# ddr3_if.net
KiCad netlist of a schematic drawn in Altium Designer
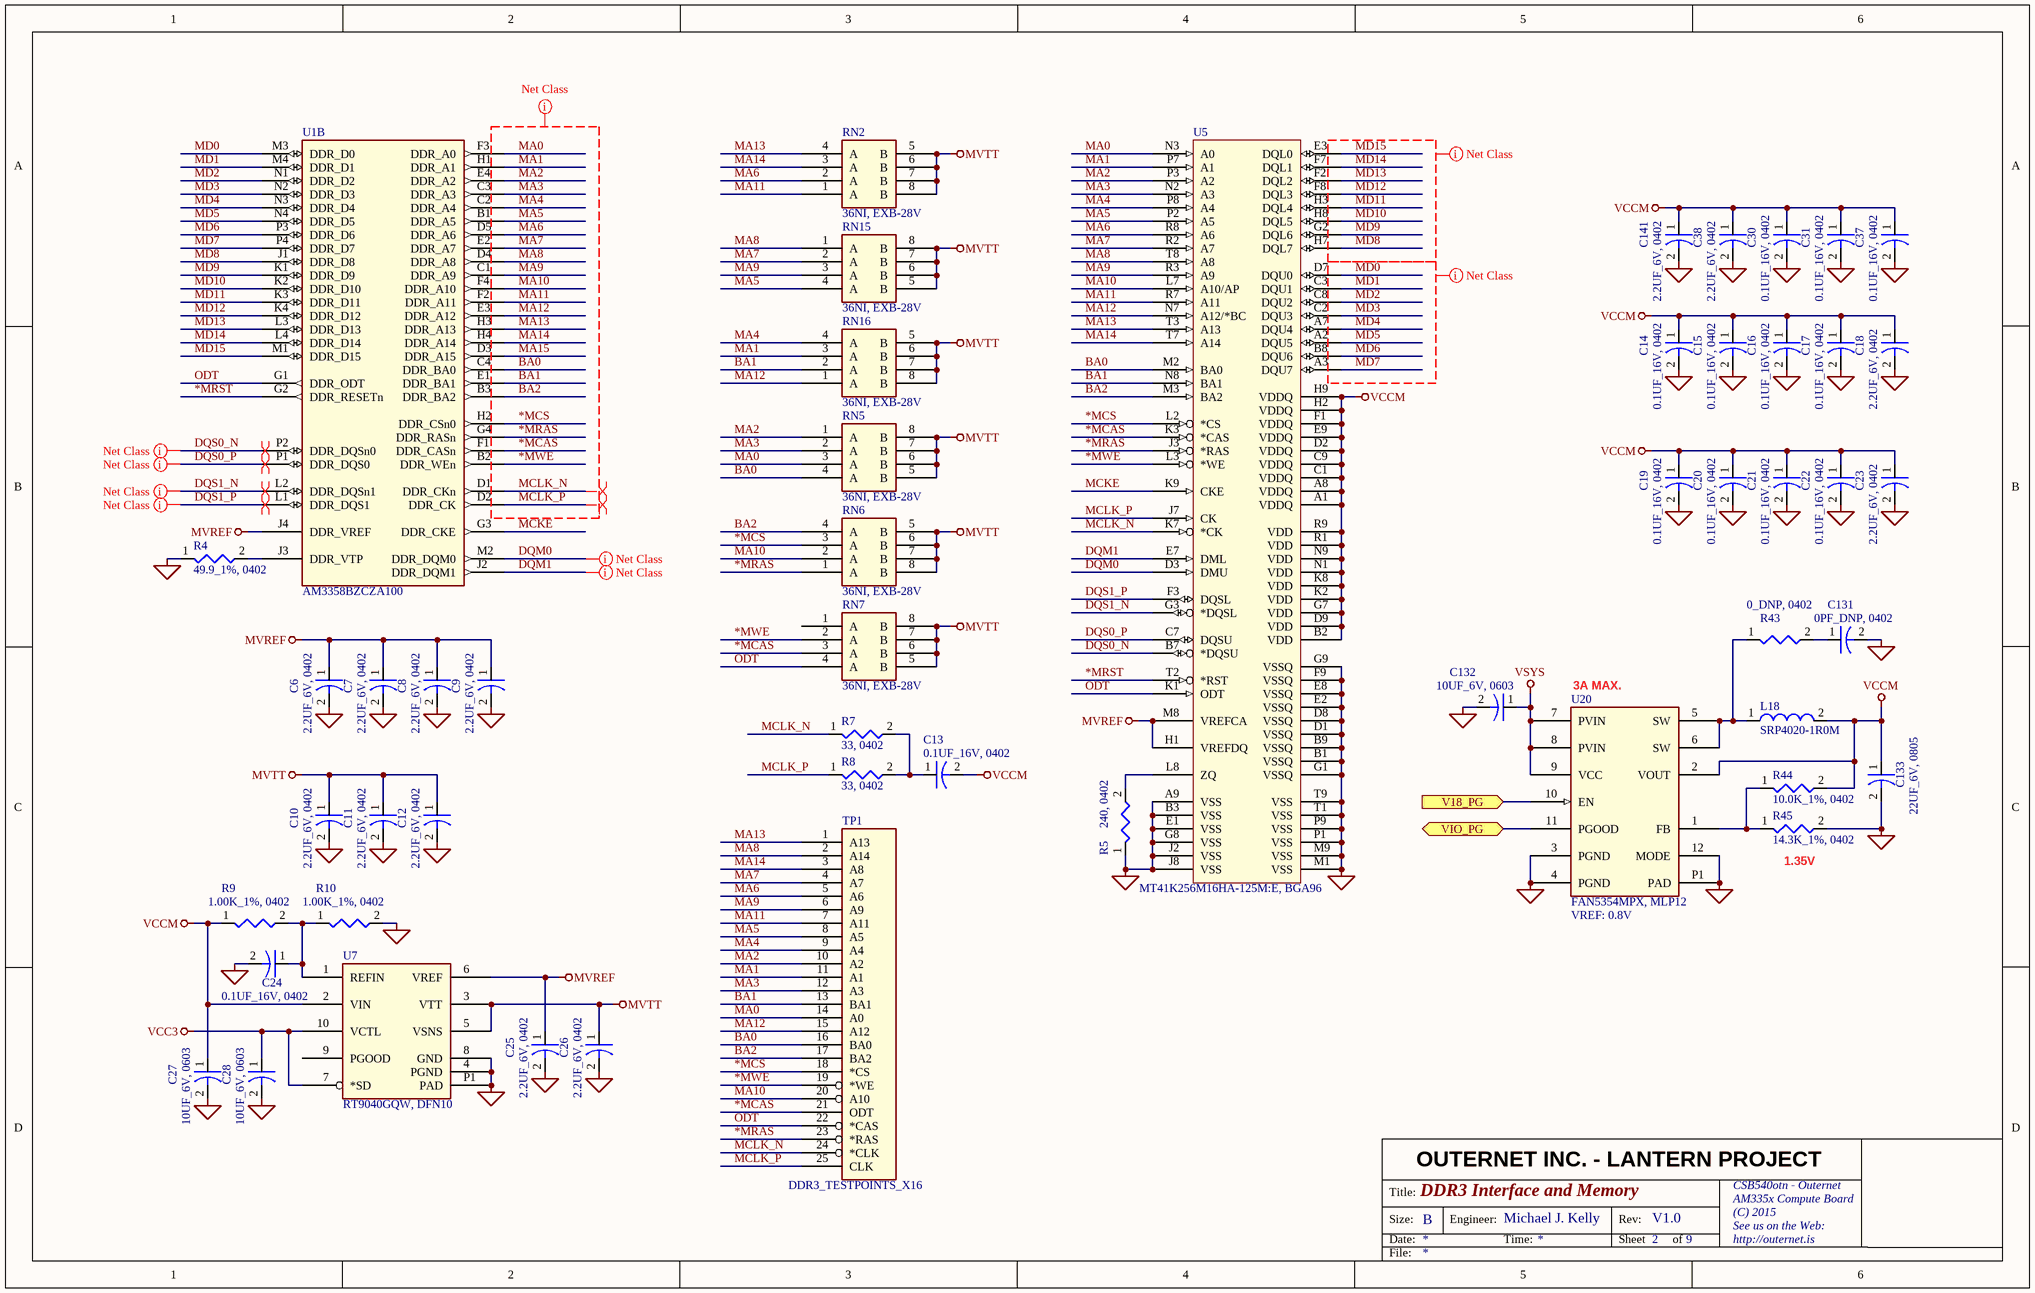
[diagram p0: ddr3_if.SchDoc]

(export (version "E")
  (design (tool "Eeschema 10.0.6"))
  (components
    (comp (ref "C6")
      (value "2.2UF_6V, 0402")
      (footprint "0402C")
      (description "CAP - 0402 PKG")
      (libsource (lib "COGENT_Library") (part "2.2UF_6V, 0402"))
    )
    (comp (ref "C7")
      (value "2.2UF_6V, 0402")
      (footprint "0402C")
      (description "CAP - 0402 PKG")
      (libsource (lib "COGENT_Library") (part "2.2UF_6V, 0402"))
    )
    (comp (ref "C8")
      (value "2.2UF_6V, 0402")
      (footprint "0402C")
      (description "CAP - 0402 PKG")
      (libsource (lib "COGENT_Library") (part "2.2UF_6V, 0402"))
    )
    (comp (ref "C9")
      (value "2.2UF_6V, 0402")
      (footprint "0402C")
      (description "CAP - 0402 PKG")
      (libsource (lib "COGENT_Library") (part "2.2UF_6V, 0402"))
    )
    (comp (ref "C10")
      (value "2.2UF_6V, 0402")
      (footprint "0402C")
      (description "CAP - 0402 PKG")
      (libsource (lib "COGENT_Library") (part "2.2UF_6V, 0402"))
    )
    (comp (ref "C11")
      (value "2.2UF_6V, 0402")
      (footprint "0402C")
      (description "CAP - 0402 PKG")
      (libsource (lib "COGENT_Library") (part "2.2UF_6V, 0402"))
    )
    (comp (ref "C12")
      (value "2.2UF_6V, 0402")
      (footprint "0402C")
      (description "CAP - 0402 PKG")
      (libsource (lib "COGENT_Library") (part "2.2UF_6V, 0402"))
    )
    (comp (ref "C13")
      (value "0.1UF_16V, 0402")
      (footprint "0402C")
      (description "CAP - 0402 PKG")
      (libsource (lib "COGENT_Library") (part "0.1UF_16V, 0402"))
    )
    (comp (ref "C14")
      (value "0.1UF_16V, 0402")
      (footprint "0402C")
      (description "CAP - 0402 PKG")
      (libsource (lib "COGENT_Library") (part "0.1UF_16V, 0402"))
    )
    (comp (ref "C15")
      (value "0.1UF_16V, 0402")
      (footprint "0402C")
      (description "CAP - 0402 PKG")
      (libsource (lib "COGENT_Library") (part "0.1UF_16V, 0402"))
    )
    (comp (ref "C16")
      (value "0.1UF_16V, 0402")
      (footprint "0402C")
      (description "CAP - 0402 PKG")
      (libsource (lib "COGENT_Library") (part "0.1UF_16V, 0402"))
    )
    (comp (ref "C17")
      (value "0.1UF_16V, 0402")
      (footprint "0402C")
      (description "CAP - 0402 PKG")
      (libsource (lib "COGENT_Library") (part "0.1UF_16V, 0402"))
    )
    (comp (ref "C18")
      (value "2.2UF_6V, 0402")
      (footprint "0402C")
      (description "CAP - 0402 PKG")
      (libsource (lib "COGENT_Library") (part "2.2UF_6V, 0402"))
    )
    (comp (ref "C19")
      (value "0.1UF_16V, 0402")
      (footprint "0402C")
      (description "CAP - 0402 PKG")
      (libsource (lib "COGENT_Library") (part "0.1UF_16V, 0402"))
    )
    (comp (ref "C20")
      (value "0.1UF_16V, 0402")
      (footprint "0402C")
      (description "CAP - 0402 PKG")
      (libsource (lib "COGENT_Library") (part "0.1UF_16V, 0402"))
    )
    (comp (ref "C21")
      (value "0.1UF_16V, 0402")
      (footprint "0402C")
      (description "CAP - 0402 PKG")
      (libsource (lib "COGENT_Library") (part "0.1UF_16V, 0402"))
    )
    (comp (ref "C22")
      (value "0.1UF_16V, 0402")
      (footprint "0402C")
      (description "CAP - 0402 PKG")
      (libsource (lib "COGENT_Library") (part "0.1UF_16V, 0402"))
    )
    (comp (ref "C23")
      (value "2.2UF_6V, 0402")
      (footprint "0402C")
      (description "CAP - 0402 PKG")
      (libsource (lib "COGENT_Library") (part "2.2UF_6V, 0402"))
    )
    (comp (ref "C24")
      (value "0.1UF_16V, 0402")
      (footprint "0402C")
      (description "CAP - 0402 PKG")
      (libsource (lib "COGENT_Library") (part "0.1UF_16V, 0402"))
    )
    (comp (ref "C25")
      (value "2.2UF_6V, 0402")
      (footprint "0402C")
      (description "CAP - 0402 PKG")
      (libsource (lib "COGENT_Library") (part "2.2UF_6V, 0402"))
    )
    (comp (ref "C26")
      (value "2.2UF_6V, 0402")
      (footprint "0402C")
      (description "CAP - 0402 PKG")
      (libsource (lib "COGENT_Library") (part "2.2UF_6V, 0402"))
    )
    (comp (ref "C27")
      (value "10UF_6V, 0603")
      (footprint "0603C")
      (description "CAP - 0603 PKG")
      (libsource (lib "COGENT_Library") (part "10UF_6V, 0603"))
    )
    (comp (ref "C28")
      (value "10UF_6V, 0603")
      (footprint "0603C")
      (description "CAP - 0603 PKG")
      (libsource (lib "COGENT_Library") (part "10UF_6V, 0603"))
    )
    (comp (ref "C30")
      (value "0.1UF_16V, 0402")
      (footprint "0402C")
      (description "CAP - 0402 PKG")
      (libsource (lib "COGENT_Library") (part "0.1UF_16V, 0402"))
    )
    (comp (ref "C31")
      (value "0.1UF_16V, 0402")
      (footprint "0402C")
      (description "CAP - 0402 PKG")
      (libsource (lib "COGENT_Library") (part "0.1UF_16V, 0402"))
    )
    (comp (ref "C37")
      (value "0.1UF_16V, 0402")
      (footprint "0402C")
      (description "CAP - 0402 PKG")
      (libsource (lib "COGENT_Library") (part "0.1UF_16V, 0402"))
    )
    (comp (ref "C38")
      (value "2.2UF_6V, 0402")
      (footprint "0402C")
      (description "CAP - 0402 PKG")
      (libsource (lib "COGENT_Library") (part "2.2UF_6V, 0402"))
    )
    (comp (ref "C131")
      (value "0PF_DNP, 0402")
      (footprint "0402C")
      (description "CAP - 0402 PKG")
      (libsource (lib "COGENT_Library") (part "0PF_DNP, 0402"))
    )
    (comp (ref "C132")
      (value "10UF_6V, 0603")
      (footprint "0603C")
      (description "CAP - 0603 PKG")
      (libsource (lib "COGENT_Library") (part "10UF_6V, 0603"))
    )
    (comp (ref "C133")
      (value "22UF_6V, 0805")
      (footprint "0805C")
      (description "CAP - 0805 PKG")
      (libsource (lib "COGENT_Library") (part "22UF_6V, 0805"))
    )
    (comp (ref "C141")
      (value "2.2UF_6V, 0402")
      (footprint "0402C")
      (description "CAP - 0402 PKG")
      (libsource (lib "COGENT_Library") (part "2.2UF_6V, 0402"))
    )
    (comp (ref "L18")
      (value "SRP4020-1R0M")
      (footprint "SRP4020")
      (description "INDUCTOR - 1.0UH, 5/6A, 4MM x 4MM x 2MM, 22mohm")
      (libsource (lib "COGENT_Library") (part "SRP4020-1R0M"))
    )
    (comp (ref "R4")
      (value "49.9_1%, 0402")
      (footprint "0402R")
      (description "RES - 0402 PKG")
      (libsource (lib "COGENT_Library") (part "49.9_1%, 0402"))
    )
    (comp (ref "R5")
      (value "240, 0402")
      (footprint "0402R")
      (description "RES - 0402 PKG")
      (libsource (lib "COGENT_Library") (part "240, 0402"))
    )
    (comp (ref "R7")
      (value "33, 0402")
      (footprint "0402R")
      (description "RES - 0402 PKG")
      (libsource (lib "COGENT_Library") (part "33, 0402"))
    )
    (comp (ref "R8")
      (value "33, 0402")
      (footprint "0402R")
      (description "RES - 0402 PKG")
      (libsource (lib "COGENT_Library") (part "33, 0402"))
    )
    (comp (ref "R9")
      (value "1.00K_1%, 0402")
      (footprint "0402R")
      (description "RES - 0402 PKG")
      (libsource (lib "COGENT_Library") (part "1.00K_1%, 0402"))
    )
    (comp (ref "R10")
      (value "1.00K_1%, 0402")
      (footprint "0402R")
      (description "RES - 0402 PKG")
      (libsource (lib "COGENT_Library") (part "1.00K_1%, 0402"))
    )
    (comp (ref "R43")
      (value "0_DNP, 0402")
      (footprint "0402R")
      (description "RES - 0402 PKG, DO NOT POPULATE BY DEFAULT")
      (libsource (lib "COGENT_Library") (part "0_DNP, 0402"))
    )
    (comp (ref "R44")
      (value "10.0K_1%, 0402")
      (footprint "0402R")
      (description "RES - 0402 PKG")
      (libsource (lib "COGENT_Library") (part "10.0K_1%, 0402"))
    )
    (comp (ref "R45")
      (value "14.3K_1%, 0402")
      (footprint "0402R")
      (description "RES - 0402 PKG")
      (libsource (lib "COGENT_Library") (part "14.3K_1%, 0402"))
    )
    (comp (ref "RN2")
      (value "36NI, EXB-28V")
      (footprint "EXB-28V")
      (description "RES NET, 4 INDIVIDUAL, EXB-28V")
      (libsource (lib "COGENT_Library") (part "36NI, EXB-28V"))
    )
    (comp (ref "RN5")
      (value "36NI, EXB-28V")
      (footprint "EXB-28V")
      (description "RES NET, 4 INDIVIDUAL, EXB-28V")
      (libsource (lib "") (part "36NI, EXB-28V_1"))
    )
    (comp (ref "RN6")
      (value "36NI, EXB-28V")
      (footprint "EXB-28V")
      (description "RES NET, 4 INDIVIDUAL, EXB-28V")
      (libsource (lib "COGENT_Library") (part "36NI, EXB-28V"))
    )
    (comp (ref "RN7")
      (value "36NI, EXB-28V")
      (footprint "EXB-28V")
      (description "RES NET, 4 INDIVIDUAL, EXB-28V")
      (libsource (lib "") (part "36NI, EXB-28V_1"))
    )
    (comp (ref "RN15")
      (value "36NI, EXB-28V")
      (footprint "EXB-28V")
      (description "RES NET, 4 INDIVIDUAL, EXB-28V")
      (libsource (lib "") (part "36NI, EXB-28V_1"))
    )
    (comp (ref "RN16")
      (value "36NI, EXB-28V")
      (footprint "EXB-28V")
      (description "RES NET, 4 INDIVIDUAL, EXB-28V")
      (libsource (lib "COGENT_Library") (part "36NI, EXB-28V"))
    )
    (comp (ref "TP1")
      (value "DDR3_TESTPOINTS_X16")
      (footprint "DDR2-TP")
      (description "MISC - DDR3 ROUTING PATTERN, 16-BIT")
      (libsource (lib "COGENT_Library") (part "DDR3_TESTPOINTS_X16"))
    )
    (comp (ref "U1")
      (value "AM3358BZCZA100")
      (footprint "BGA324x18")
      (description "MPU - CORTEX-A8 CORE, SDIO, GIGe, USB x2, UART x3, CAN, 2D/3D")
      (libsource (lib "COGENT_Library") (part "AM3358BZCZA100"))
    )
    (comp (ref "U5")
      (value "MT41K256M16HA-125M:E, BGA96")
      (footprint "BGA96_DDR3_X16")
      (description "SDRAM - 4GBIT, DDR3/L-1600, x16")
      (libsource (lib "COGENT_Library") (part "MT41K256M16HA-125M{colon}E, BGA96"))
    )
    (comp (ref "U7")
      (value "RT9040GQW, DFN10")
      (footprint "DFN10")
      (description "LDO - DDR2/3 VREF AND VTT, 3A")
      (libsource (lib "COGENT_Library") (part "RT9040GQW, DFN10"))
    )
    (comp (ref "U20")
      (value "FAN5354MPX, MLP12")
      (footprint "mlp12")
      (description "SWITCHER - 270ua Iq, 3A, 2.7V TO 5.5V IN, 0.8V TO VIN OUT")
      (fields (field (name "VREF") "0.8V"))
      (libsource (lib "COGENT_Library") (part "FAN5354MPX, MLP12"))
    )
  )
  (nets
    (net (code "1") (name "/*MCAS") (class "Default")
      (node (ref "RN7") (pin "3") (pinfunction "A_3") (pintype "passive"))
      (node (ref "TP1") (pin "21") (pinfunction "ODT_21") (pintype "passive"))
      (node (ref "U1") (pin "F1") (pinfunction "DDR_CASn_F1") (pintype "output"))
      (node (ref "U5") (pin "K3") (pinfunction "*CAS_K3") (pintype "input"))
    )
    (net (code "2") (name "/*MCS") (class "Default")
      (node (ref "RN6") (pin "3") (pinfunction "A_3") (pintype "passive"))
      (node (ref "TP1") (pin "18") (pinfunction "*CS_18") (pintype "passive"))
      (node (ref "U1") (pin "H2") (pinfunction "DDR_CSn0_H2") (pintype "output"))
      (node (ref "U5") (pin "L2") (pinfunction "*CS_L2") (pintype "input"))
    )
    (net (code "3") (name "/*MRAS") (class "Default")
      (node (ref "RN6") (pin "1") (pinfunction "A_1") (pintype "passive"))
      (node (ref "TP1") (pin "23") (pinfunction "*RAS_23") (pintype "passive"))
      (node (ref "U1") (pin "G4") (pinfunction "DDR_RASn_G4") (pintype "output"))
      (node (ref "U5") (pin "J3") (pinfunction "*RAS_J3") (pintype "input"))
    )
    (net (code "4") (name "/*MRST") (class "Default")
      (node (ref "U1") (pin "G2") (pinfunction "DDR_RESETn_G2") (pintype "output"))
      (node (ref "U5") (pin "T2") (pinfunction "*RST_T2") (pintype "input"))
    )
    (net (code "5") (name "/*MWE") (class "Default")
      (node (ref "RN7") (pin "2") (pinfunction "A_2") (pintype "passive"))
      (node (ref "TP1") (pin "19") (pinfunction "*WE_19") (pintype "passive"))
      (node (ref "U1") (pin "B2") (pinfunction "DDR_WEn_B2") (pintype "output"))
      (node (ref "U5") (pin "L3") (pinfunction "*WE_L3") (pintype "input"))
    )
    (net (code "6") (name "/BA0") (class "Default")
      (node (ref "RN5") (pin "4") (pinfunction "A_4") (pintype "passive"))
      (node (ref "TP1") (pin "16") (pinfunction "BA0_16") (pintype "passive"))
      (node (ref "U1") (pin "C4") (pinfunction "DDR_BA0_C4") (pintype "output"))
      (node (ref "U5") (pin "M2") (pinfunction "BA0_M2") (pintype "input"))
    )
    (net (code "7") (name "/BA1") (class "Default")
      (node (ref "RN16") (pin "2") (pinfunction "A_2") (pintype "passive"))
      (node (ref "TP1") (pin "13") (pinfunction "BA1_13") (pintype "passive"))
      (node (ref "U1") (pin "E1") (pinfunction "DDR_BA1_E1") (pintype "output"))
      (node (ref "U5") (pin "N8") (pinfunction "BA1_N8") (pintype "input"))
    )
    (net (code "8") (name "/BA2") (class "Default")
      (node (ref "RN6") (pin "4") (pinfunction "A_4") (pintype "passive"))
      (node (ref "TP1") (pin "17") (pinfunction "BA2_17") (pintype "passive"))
      (node (ref "U1") (pin "B3") (pinfunction "DDR_BA2_B3") (pintype "output"))
      (node (ref "U5") (pin "M3") (pinfunction "BA2_M3") (pintype "input"))
    )
    (net (code "9") (name "/DQM0") (class "Default")
      (node (ref "U1") (pin "M2") (pinfunction "DDR_DQM0_M2") (pintype "output"))
      (node (ref "U5") (pin "D3") (pinfunction "DMU_D3") (pintype "input"))
    )
    (net (code "10") (name "/DQM1") (class "Default")
      (node (ref "U1") (pin "J2") (pinfunction "DDR_DQM1_J2") (pintype "output"))
      (node (ref "U5") (pin "E7") (pinfunction "DML_E7") (pintype "input"))
    )
    (net (code "11") (name "/DQS0_N") (class "Default")
      (node (ref "U1") (pin "P2") (pinfunction "DDR_DQSn0_P2") (pintype "bidirectional"))
      (node (ref "U5") (pin "B7") (pinfunction "*DQSU_B7") (pintype "bidirectional"))
    )
    (net (code "12") (name "/DQS0_P") (class "Default")
      (node (ref "U1") (pin "P1") (pinfunction "DDR_DQS0_P1") (pintype "bidirectional"))
      (node (ref "U5") (pin "C7") (pinfunction "DQSU_C7") (pintype "bidirectional"))
    )
    (net (code "13") (name "/DQS1_N") (class "Default")
      (node (ref "U1") (pin "L2") (pinfunction "DDR_DQSn1_L2") (pintype "bidirectional"))
      (node (ref "U5") (pin "G3") (pinfunction "*DQSL_G3") (pintype "bidirectional"))
    )
    (net (code "14") (name "/DQS1_P") (class "Default")
      (node (ref "U1") (pin "L1") (pinfunction "DDR_DQS1_L1") (pintype "bidirectional"))
      (node (ref "U5") (pin "F3") (pinfunction "DQSL_F3") (pintype "bidirectional"))
    )
    (net (code "15") (name "/MA0") (class "Default")
      (node (ref "RN5") (pin "3") (pinfunction "A_3") (pintype "passive"))
      (node (ref "TP1") (pin "14") (pinfunction "A0_14") (pintype "passive"))
      (node (ref "U1") (pin "F3") (pinfunction "DDR_A0_F3") (pintype "output"))
      (node (ref "U5") (pin "N3") (pinfunction "A0_N3") (pintype "input"))
    )
    (net (code "16") (name "/MA1") (class "Default")
      (node (ref "RN16") (pin "3") (pinfunction "A_3") (pintype "passive"))
      (node (ref "TP1") (pin "11") (pinfunction "A1_11") (pintype "passive"))
      (node (ref "U1") (pin "H1") (pinfunction "DDR_A1_H1") (pintype "output"))
      (node (ref "U5") (pin "P7") (pinfunction "A1_P7") (pintype "input"))
    )
    (net (code "17") (name "/MA2") (class "Default")
      (node (ref "RN5") (pin "1") (pinfunction "A_1") (pintype "passive"))
      (node (ref "TP1") (pin "10") (pinfunction "A2_10") (pintype "passive"))
      (node (ref "U1") (pin "E4") (pinfunction "DDR_A2_E4") (pintype "output"))
      (node (ref "U5") (pin "P3") (pinfunction "A2_P3") (pintype "input"))
    )
    (net (code "18") (name "/MA3") (class "Default")
      (node (ref "RN5") (pin "2") (pinfunction "A_2") (pintype "passive"))
      (node (ref "TP1") (pin "12") (pinfunction "A3_12") (pintype "passive"))
      (node (ref "U1") (pin "C3") (pinfunction "DDR_A3_C3") (pintype "output"))
      (node (ref "U5") (pin "N2") (pinfunction "A3_N2") (pintype "input"))
    )
    (net (code "19") (name "/MA4") (class "Default")
      (node (ref "RN16") (pin "4") (pinfunction "A_4") (pintype "passive"))
      (node (ref "TP1") (pin "9") (pinfunction "A4_9") (pintype "passive"))
      (node (ref "U1") (pin "C2") (pinfunction "DDR_A4_C2") (pintype "output"))
      (node (ref "U5") (pin "P8") (pinfunction "A4_P8") (pintype "input"))
    )
    (net (code "20") (name "/MA5") (class "Default")
      (node (ref "RN15") (pin "4") (pinfunction "A_4") (pintype "passive"))
      (node (ref "TP1") (pin "8") (pinfunction "A5_8") (pintype "passive"))
      (node (ref "U1") (pin "B1") (pinfunction "DDR_A5_B1") (pintype "output"))
      (node (ref "U5") (pin "P2") (pinfunction "A5_P2") (pintype "input"))
    )
    (net (code "21") (name "/MA6") (class "Default")
      (node (ref "RN2") (pin "2") (pinfunction "A_2") (pintype "passive"))
      (node (ref "TP1") (pin "5") (pinfunction "A6_5") (pintype "passive"))
      (node (ref "U1") (pin "D5") (pinfunction "DDR_A6_D5") (pintype "output"))
      (node (ref "U5") (pin "R8") (pinfunction "A6_R8") (pintype "input"))
    )
    (net (code "22") (name "/MA7") (class "Default")
      (node (ref "RN15") (pin "2") (pinfunction "A_2") (pintype "passive"))
      (node (ref "TP1") (pin "4") (pinfunction "A7_4") (pintype "passive"))
      (node (ref "U1") (pin "E2") (pinfunction "DDR_A7_E2") (pintype "output"))
      (node (ref "U5") (pin "R2") (pinfunction "A7_R2") (pintype "input"))
    )
    (net (code "23") (name "/MA8") (class "Default")
      (node (ref "RN15") (pin "1") (pinfunction "A_1") (pintype "passive"))
      (node (ref "TP1") (pin "2") (pinfunction "A14_2") (pintype "passive"))
      (node (ref "U1") (pin "D4") (pinfunction "DDR_A8_D4") (pintype "output"))
      (node (ref "U5") (pin "T8") (pinfunction "A8_T8") (pintype "input"))
    )
    (net (code "24") (name "/MA9") (class "Default")
      (node (ref "RN15") (pin "3") (pinfunction "A_3") (pintype "passive"))
      (node (ref "TP1") (pin "6") (pinfunction "A9_6") (pintype "passive"))
      (node (ref "U1") (pin "C1") (pinfunction "DDR_A9_C1") (pintype "output"))
      (node (ref "U5") (pin "R3") (pinfunction "A9_R3") (pintype "input"))
    )
    (net (code "25") (name "/MA10") (class "Default")
      (node (ref "RN6") (pin "2") (pinfunction "A_2") (pintype "passive"))
      (node (ref "TP1") (pin "20") (pinfunction "A10_20") (pintype "passive"))
      (node (ref "U1") (pin "F4") (pinfunction "DDR_A10_F4") (pintype "output"))
      (node (ref "U5") (pin "L7") (pinfunction "A10/AP_L7") (pintype "input"))
    )
    (net (code "26") (name "/MA11") (class "Default")
      (node (ref "RN2") (pin "1") (pinfunction "A_1") (pintype "passive"))
      (node (ref "TP1") (pin "7") (pinfunction "A11_7") (pintype "passive"))
      (node (ref "U1") (pin "F2") (pinfunction "DDR_A11_F2") (pintype "output"))
      (node (ref "U5") (pin "R7") (pinfunction "A11_R7") (pintype "input"))
    )
    (net (code "27") (name "/MA12") (class "Default")
      (node (ref "RN16") (pin "1") (pinfunction "A_1") (pintype "passive"))
      (node (ref "TP1") (pin "15") (pinfunction "A12_15") (pintype "passive"))
      (node (ref "U1") (pin "E3") (pinfunction "DDR_A12_E3") (pintype "output"))
      (node (ref "U5") (pin "N7") (pinfunction "A12/*BC_N7") (pintype "input"))
    )
    (net (code "28") (name "/MA13") (class "Default")
      (node (ref "RN2") (pin "4") (pinfunction "A_4") (pintype "passive"))
      (node (ref "TP1") (pin "1") (pinfunction "A13_1") (pintype "passive"))
      (node (ref "U1") (pin "H3") (pinfunction "DDR_A13_H3") (pintype "output"))
      (node (ref "U5") (pin "T3") (pinfunction "A13_T3") (pintype "input"))
    )
    (net (code "29") (name "/MA14") (class "Default")
      (node (ref "RN2") (pin "3") (pinfunction "A_3") (pintype "passive"))
      (node (ref "TP1") (pin "3") (pinfunction "A8_3") (pintype "passive"))
      (node (ref "U1") (pin "H4") (pinfunction "DDR_A14_H4") (pintype "output"))
      (node (ref "U5") (pin "T7") (pinfunction "A14_T7") (pintype "input"))
    )
    (net (code "30") (name "/MA15") (class "Default")
      (node (ref "U1") (pin "D3") (pinfunction "DDR_A15_D3") (pintype "output"))
    )
    (net (code "31") (name "/MCKE") (class "Default")
      (node (ref "U1") (pin "G3") (pinfunction "DDR_CKE_G3") (pintype "output"))
      (node (ref "U5") (pin "K9") (pinfunction "CKE_K9") (pintype "input"))
    )
    (net (code "32") (name "/MCLK_N") (class "Default")
      (node (ref "R7") (pin "1") (pinfunction "1_1") (pintype "passive"))
      (node (ref "TP1") (pin "24") (pinfunction "*CLK_24") (pintype "passive"))
      (node (ref "U1") (pin "D1") (pinfunction "DDR_CKn_D1") (pintype "output"))
      (node (ref "U5") (pin "K7") (pinfunction "*CK_K7") (pintype "input"))
    )
    (net (code "33") (name "/MCLK_P") (class "Default")
      (node (ref "R8") (pin "1") (pinfunction "1_1") (pintype "passive"))
      (node (ref "TP1") (pin "25") (pinfunction "CLK_25") (pintype "passive"))
      (node (ref "U1") (pin "D2") (pinfunction "DDR_CK_D2") (pintype "output"))
      (node (ref "U5") (pin "J7") (pinfunction "CK_J7") (pintype "input"))
    )
    (net (code "34") (name "/MD0") (class "Default")
      (node (ref "U1") (pin "M3") (pinfunction "DDR_D0_M3") (pintype "bidirectional"))
      (node (ref "U5") (pin "D7") (pinfunction "DQU0_D7") (pintype "bidirectional"))
    )
    (net (code "35") (name "/MD1") (class "Default")
      (node (ref "U1") (pin "M4") (pinfunction "DDR_D1_M4") (pintype "bidirectional"))
      (node (ref "U5") (pin "C3") (pinfunction "DQU1_C3") (pintype "bidirectional"))
    )
    (net (code "36") (name "/MD2") (class "Default")
      (node (ref "U1") (pin "N1") (pinfunction "DDR_D2_N1") (pintype "bidirectional"))
      (node (ref "U5") (pin "C8") (pinfunction "DQU2_C8") (pintype "bidirectional"))
    )
    (net (code "37") (name "/MD3") (class "Default")
      (node (ref "U1") (pin "N2") (pinfunction "DDR_D3_N2") (pintype "bidirectional"))
      (node (ref "U5") (pin "C2") (pinfunction "DQU3_C2") (pintype "bidirectional"))
    )
    (net (code "38") (name "/MD4") (class "Default")
      (node (ref "U1") (pin "N3") (pinfunction "DDR_D4_N3") (pintype "bidirectional"))
      (node (ref "U5") (pin "A7") (pinfunction "DQU4_A7") (pintype "bidirectional"))
    )
    (net (code "39") (name "/MD5") (class "Default")
      (node (ref "U1") (pin "N4") (pinfunction "DDR_D5_N4") (pintype "bidirectional"))
      (node (ref "U5") (pin "A2") (pinfunction "DQU5_A2") (pintype "bidirectional"))
    )
    (net (code "40") (name "/MD6") (class "Default")
      (node (ref "U1") (pin "P3") (pinfunction "DDR_D6_P3") (pintype "bidirectional"))
      (node (ref "U5") (pin "B8") (pinfunction "DQU6_B8") (pintype "bidirectional"))
    )
    (net (code "41") (name "/MD7") (class "Default")
      (node (ref "U1") (pin "P4") (pinfunction "DDR_D7_P4") (pintype "bidirectional"))
      (node (ref "U5") (pin "A3") (pinfunction "DQU7_A3") (pintype "bidirectional"))
    )
    (net (code "42") (name "/MD8") (class "Default")
      (node (ref "U1") (pin "J1") (pinfunction "DDR_D8_J1") (pintype "bidirectional"))
      (node (ref "U5") (pin "H7") (pinfunction "DQL7_H7") (pintype "bidirectional"))
    )
    (net (code "43") (name "/MD9") (class "Default")
      (node (ref "U1") (pin "K1") (pinfunction "DDR_D9_K1") (pintype "bidirectional"))
      (node (ref "U5") (pin "G2") (pinfunction "DQL6_G2") (pintype "bidirectional"))
    )
    (net (code "44") (name "/MD10") (class "Default")
      (node (ref "U1") (pin "K2") (pinfunction "DDR_D10_K2") (pintype "bidirectional"))
      (node (ref "U5") (pin "H8") (pinfunction "DQL5_H8") (pintype "bidirectional"))
    )
    (net (code "45") (name "/MD11") (class "Default")
      (node (ref "U1") (pin "K3") (pinfunction "DDR_D11_K3") (pintype "bidirectional"))
      (node (ref "U5") (pin "H3") (pinfunction "DQL4_H3") (pintype "bidirectional"))
    )
    (net (code "46") (name "/MD12") (class "Default")
      (node (ref "U1") (pin "K4") (pinfunction "DDR_D12_K4") (pintype "bidirectional"))
      (node (ref "U5") (pin "F8") (pinfunction "DQL3_F8") (pintype "bidirectional"))
    )
    (net (code "47") (name "/MD13") (class "Default")
      (node (ref "U1") (pin "L3") (pinfunction "DDR_D13_L3") (pintype "bidirectional"))
      (node (ref "U5") (pin "F2") (pinfunction "DQL2_F2") (pintype "bidirectional"))
    )
    (net (code "48") (name "/MD14") (class "Default")
      (node (ref "U1") (pin "L4") (pinfunction "DDR_D14_L4") (pintype "bidirectional"))
      (node (ref "U5") (pin "F7") (pinfunction "DQL1_F7") (pintype "bidirectional"))
    )
    (net (code "49") (name "/MD15") (class "Default")
      (node (ref "U1") (pin "M1") (pinfunction "DDR_D15_M1") (pintype "bidirectional"))
      (node (ref "U5") (pin "E3") (pinfunction "DQL0_E3") (pintype "bidirectional"))
    )
    (net (code "50") (name "/ODT") (class "Default")
      (node (ref "RN7") (pin "4") (pinfunction "A_4") (pintype "passive"))
      (node (ref "TP1") (pin "22") (pinfunction "*CAS_22") (pintype "passive"))
      (node (ref "U1") (pin "G1") (pinfunction "DDR_ODT_G1") (pintype "output"))
      (node (ref "U5") (pin "K1") (pinfunction "ODT_K1") (pintype "input"))
    )
    (net (code "51") (name "/V18_PG") (class "Default")
      (node (ref "U20") (pin "10") (pinfunction "EN_10") (pintype "input"))
    )
    (net (code "52") (name "/VIO_PG") (class "Default")
      (node (ref "U20") (pin "11") (pinfunction "PGOOD_11") (pintype "open_collector"))
    )
    (net (code "53") (name "GND") (class "Default")
      (node (ref "C10") (pin "2") (pinfunction "2_2") (pintype "passive"))
      (node (ref "C11") (pin "2") (pinfunction "2_2") (pintype "passive"))
      (node (ref "C12") (pin "2") (pinfunction "2_2") (pintype "passive"))
      (node (ref "C131") (pin "2") (pinfunction "2_2") (pintype "passive"))
      (node (ref "C132") (pin "2") (pinfunction "2_2") (pintype "passive"))
      (node (ref "C133") (pin "2") (pinfunction "2_2") (pintype "passive"))
      (node (ref "C14") (pin "2") (pinfunction "2_2") (pintype "passive"))
      (node (ref "C141") (pin "2") (pinfunction "2_2") (pintype "passive"))
      (node (ref "C15") (pin "2") (pinfunction "2_2") (pintype "passive"))
      (node (ref "C16") (pin "2") (pinfunction "2_2") (pintype "passive"))
      (node (ref "C17") (pin "2") (pinfunction "2_2") (pintype "passive"))
      (node (ref "C18") (pin "2") (pinfunction "2_2") (pintype "passive"))
      (node (ref "C19") (pin "2") (pinfunction "2_2") (pintype "passive"))
      (node (ref "C20") (pin "2") (pinfunction "2_2") (pintype "passive"))
      (node (ref "C21") (pin "2") (pinfunction "2_2") (pintype "passive"))
      (node (ref "C22") (pin "2") (pinfunction "2_2") (pintype "passive"))
      (node (ref "C23") (pin "2") (pinfunction "2_2") (pintype "passive"))
      (node (ref "C24") (pin "2") (pinfunction "2_2") (pintype "passive"))
      (node (ref "C25") (pin "2") (pinfunction "2_2") (pintype "passive"))
      (node (ref "C26") (pin "2") (pinfunction "2_2") (pintype "passive"))
      (node (ref "C27") (pin "2") (pinfunction "2_2") (pintype "passive"))
      (node (ref "C28") (pin "2") (pinfunction "2_2") (pintype "passive"))
      (node (ref "C30") (pin "2") (pinfunction "2_2") (pintype "passive"))
      (node (ref "C31") (pin "2") (pinfunction "2_2") (pintype "passive"))
      (node (ref "C37") (pin "2") (pinfunction "2_2") (pintype "passive"))
      (node (ref "C38") (pin "2") (pinfunction "2_2") (pintype "passive"))
      (node (ref "C6") (pin "2") (pinfunction "2_2") (pintype "passive"))
      (node (ref "C7") (pin "2") (pinfunction "2_2") (pintype "passive"))
      (node (ref "C8") (pin "2") (pinfunction "2_2") (pintype "passive"))
      (node (ref "C9") (pin "2") (pinfunction "2_2") (pintype "passive"))
      (node (ref "R10") (pin "2") (pinfunction "2_2") (pintype "passive"))
      (node (ref "R4") (pin "1") (pinfunction "1_1") (pintype "passive"))
      (node (ref "R45") (pin "2") (pinfunction "2_2") (pintype "passive"))
      (node (ref "R5") (pin "1") (pinfunction "1_1") (pintype "passive"))
      (node (ref "U20") (pin "12") (pinfunction "MODE_12") (pintype "passive"))
      (node (ref "U20") (pin "3") (pinfunction "PGND_3") (pintype "power_in"))
      (node (ref "U20") (pin "4") (pinfunction "PGND_4") (pintype "power_in"))
      (node (ref "U20") (pin "P1") (pinfunction "PAD_P1") (pintype "power_in"))
      (node (ref "U5") (pin "A9") (pinfunction "VSS_A9") (pintype "power_in"))
      (node (ref "U5") (pin "B1") (pinfunction "VSSQ_B1") (pintype "power_in"))
      (node (ref "U5") (pin "B3") (pinfunction "VSS_B3") (pintype "power_in"))
      (node (ref "U5") (pin "B9") (pinfunction "VSSQ_B9") (pintype "power_in"))
      (node (ref "U5") (pin "D1") (pinfunction "VSSQ_D1") (pintype "power_in"))
      (node (ref "U5") (pin "D8") (pinfunction "VSSQ_D8") (pintype "power_in"))
      (node (ref "U5") (pin "E1") (pinfunction "VSS_E1") (pintype "power_in"))
      (node (ref "U5") (pin "E2") (pinfunction "VSSQ_E2") (pintype "power_in"))
      (node (ref "U5") (pin "E8") (pinfunction "VSSQ_E8") (pintype "power_in"))
      (node (ref "U5") (pin "F9") (pinfunction "VSSQ_F9") (pintype "power_in"))
      (node (ref "U5") (pin "G1") (pinfunction "VSSQ_G1") (pintype "power_in"))
      (node (ref "U5") (pin "G8") (pinfunction "VSS_G8") (pintype "power_in"))
      (node (ref "U5") (pin "G9") (pinfunction "VSSQ_G9") (pintype "power_in"))
      (node (ref "U5") (pin "J2") (pinfunction "VSS_J2") (pintype "power_in"))
      (node (ref "U5") (pin "J8") (pinfunction "VSS_J8") (pintype "power_in"))
      (node (ref "U5") (pin "M1") (pinfunction "VSS_M1") (pintype "power_in"))
      (node (ref "U5") (pin "M9") (pinfunction "VSS_M9") (pintype "power_in"))
      (node (ref "U5") (pin "P1") (pinfunction "VSS_P1") (pintype "power_in"))
      (node (ref "U5") (pin "P9") (pinfunction "VSS_P9") (pintype "power_in"))
      (node (ref "U5") (pin "T1") (pinfunction "VSS_T1") (pintype "power_in"))
      (node (ref "U5") (pin "T9") (pinfunction "VSS_T9") (pintype "power_in"))
      (node (ref "U7") (pin "4") (pinfunction "PGND_4") (pintype "power_in"))
      (node (ref "U7") (pin "8") (pinfunction "GND_8") (pintype "power_in"))
      (node (ref "U7") (pin "P1") (pinfunction "PAD_P1") (pintype "power_in"))
    )
    (net (code "54") (name "MVREF") (class "Default")
      (node (ref "C25") (pin "1") (pinfunction "1_1") (pintype "passive"))
      (node (ref "C6") (pin "1") (pinfunction "1_1") (pintype "passive"))
      (node (ref "C7") (pin "1") (pinfunction "1_1") (pintype "passive"))
      (node (ref "C8") (pin "1") (pinfunction "1_1") (pintype "passive"))
      (node (ref "C9") (pin "1") (pinfunction "1_1") (pintype "passive"))
      (node (ref "U1") (pin "J4") (pinfunction "DDR_VREF_J4") (pintype "passive"))
      (node (ref "U5") (pin "H1") (pinfunction "VREFDQ_H1") (pintype "passive"))
      (node (ref "U5") (pin "M8") (pinfunction "VREFCA_M8") (pintype "passive"))
      (node (ref "U7") (pin "6") (pinfunction "VREF_6") (pintype "power_in"))
    )
    (net (code "55") (name "MVTT") (class "Default")
      (node (ref "C10") (pin "1") (pinfunction "1_1") (pintype "passive"))
      (node (ref "C11") (pin "1") (pinfunction "1_1") (pintype "passive"))
      (node (ref "C12") (pin "1") (pinfunction "1_1") (pintype "passive"))
      (node (ref "C26") (pin "1") (pinfunction "1_1") (pintype "passive"))
      (node (ref "RN15") (pin "5") (pinfunction "B_5") (pintype "passive"))
      (node (ref "RN15") (pin "6") (pinfunction "B_6") (pintype "passive"))
      (node (ref "RN15") (pin "7") (pinfunction "B_7") (pintype "passive"))
      (node (ref "RN15") (pin "8") (pinfunction "B_8") (pintype "passive"))
      (node (ref "RN16") (pin "5") (pinfunction "B_5") (pintype "passive"))
      (node (ref "RN16") (pin "6") (pinfunction "B_6") (pintype "passive"))
      (node (ref "RN16") (pin "7") (pinfunction "B_7") (pintype "passive"))
      (node (ref "RN16") (pin "8") (pinfunction "B_8") (pintype "passive"))
      (node (ref "RN2") (pin "5") (pinfunction "B_5") (pintype "passive"))
      (node (ref "RN2") (pin "6") (pinfunction "B_6") (pintype "passive"))
      (node (ref "RN2") (pin "7") (pinfunction "B_7") (pintype "passive"))
      (node (ref "RN2") (pin "8") (pinfunction "B_8") (pintype "passive"))
      (node (ref "RN5") (pin "5") (pinfunction "B_5") (pintype "passive"))
      (node (ref "RN5") (pin "6") (pinfunction "B_6") (pintype "passive"))
      (node (ref "RN5") (pin "7") (pinfunction "B_7") (pintype "passive"))
      (node (ref "RN5") (pin "8") (pinfunction "B_8") (pintype "passive"))
      (node (ref "RN6") (pin "5") (pinfunction "B_5") (pintype "passive"))
      (node (ref "RN6") (pin "6") (pinfunction "B_6") (pintype "passive"))
      (node (ref "RN6") (pin "7") (pinfunction "B_7") (pintype "passive"))
      (node (ref "RN6") (pin "8") (pinfunction "B_8") (pintype "passive"))
      (node (ref "RN7") (pin "5") (pinfunction "B_5") (pintype "passive"))
      (node (ref "RN7") (pin "6") (pinfunction "B_6") (pintype "passive"))
      (node (ref "RN7") (pin "7") (pinfunction "B_7") (pintype "passive"))
      (node (ref "RN7") (pin "8") (pinfunction "B_8") (pintype "passive"))
      (node (ref "U7") (pin "3") (pinfunction "VTT_3") (pintype "power_in"))
      (node (ref "U7") (pin "5") (pinfunction "VSNS_5") (pintype "power_in"))
    )
    (net (code "56") (name "Net-(C13-Pad1)") (class "Default")
      (node (ref "C13") (pin "1") (pinfunction "1_1") (pintype "passive"))
      (node (ref "R7") (pin "2") (pinfunction "2_2") (pintype "passive"))
      (node (ref "R8") (pin "2") (pinfunction "2_2") (pintype "passive"))
    )
    (net (code "57") (name "Net-(C131-Pad1)") (class "Default")
      (node (ref "C131") (pin "1") (pinfunction "1_1") (pintype "passive"))
      (node (ref "R43") (pin "2") (pinfunction "2_2") (pintype "passive"))
    )
    (net (code "58") (name "Net-(L18-Pad1)") (class "Default")
      (node (ref "L18") (pin "1") (pinfunction "1_1") (pintype "passive"))
      (node (ref "R43") (pin "1") (pinfunction "1_1") (pintype "passive"))
      (node (ref "U20") (pin "5") (pinfunction "SW_5") (pintype "passive"))
      (node (ref "U20") (pin "6") (pinfunction "SW_6") (pintype "passive"))
    )
    (net (code "59") (name "Net-(U1B-DDR_VTP)") (class "Default")
      (node (ref "R4") (pin "2") (pinfunction "2_2") (pintype "passive"))
      (node (ref "U1") (pin "J3") (pinfunction "DDR_VTP_J3") (pintype "passive"))
    )
    (net (code "60") (name "Net-(U5-ZQ)") (class "Default")
      (node (ref "R5") (pin "2") (pinfunction "2_2") (pintype "passive"))
      (node (ref "U5") (pin "L8") (pinfunction "ZQ_L8") (pintype "passive"))
    )
    (net (code "61") (name "Net-(U7-REFIN)") (class "Default")
      (node (ref "C24") (pin "1") (pinfunction "1_1") (pintype "passive"))
      (node (ref "R10") (pin "1") (pinfunction "1_1") (pintype "passive"))
      (node (ref "R9") (pin "2") (pinfunction "2_2") (pintype "passive"))
      (node (ref "U7") (pin "1") (pinfunction "REFIN_1") (pintype "power_in"))
    )
    (net (code "62") (name "Net-(U20-FB)") (class "Default")
      (node (ref "R44") (pin "1") (pinfunction "1_1") (pintype "passive"))
      (node (ref "R45") (pin "1") (pinfunction "1_1") (pintype "passive"))
      (node (ref "U20") (pin "1") (pinfunction "FB_1") (pintype "passive"))
    )
    (net (code "63") (name "VCC3") (class "Default")
      (node (ref "C28") (pin "1") (pinfunction "1_1") (pintype "passive"))
      (node (ref "U7") (pin "10") (pinfunction "VCTL_10") (pintype "power_in"))
      (node (ref "U7") (pin "7") (pinfunction "*SD_7") (pintype "passive"))
    )
    (net (code "64") (name "VCCM") (class "Default")
      (node (ref "C13") (pin "2") (pinfunction "2_2") (pintype "passive"))
      (node (ref "C133") (pin "1") (pinfunction "1_1") (pintype "passive"))
      (node (ref "C14") (pin "1") (pinfunction "1_1") (pintype "passive"))
      (node (ref "C141") (pin "1") (pinfunction "1_1") (pintype "passive"))
      (node (ref "C15") (pin "1") (pinfunction "1_1") (pintype "passive"))
      (node (ref "C16") (pin "1") (pinfunction "1_1") (pintype "passive"))
      (node (ref "C17") (pin "1") (pinfunction "1_1") (pintype "passive"))
      (node (ref "C18") (pin "1") (pinfunction "1_1") (pintype "passive"))
      (node (ref "C19") (pin "1") (pinfunction "1_1") (pintype "passive"))
      (node (ref "C20") (pin "1") (pinfunction "1_1") (pintype "passive"))
      (node (ref "C21") (pin "1") (pinfunction "1_1") (pintype "passive"))
      (node (ref "C22") (pin "1") (pinfunction "1_1") (pintype "passive"))
      (node (ref "C23") (pin "1") (pinfunction "1_1") (pintype "passive"))
      (node (ref "C27") (pin "1") (pinfunction "1_1") (pintype "passive"))
      (node (ref "C30") (pin "1") (pinfunction "1_1") (pintype "passive"))
      (node (ref "C31") (pin "1") (pinfunction "1_1") (pintype "passive"))
      (node (ref "C37") (pin "1") (pinfunction "1_1") (pintype "passive"))
      (node (ref "C38") (pin "1") (pinfunction "1_1") (pintype "passive"))
      (node (ref "L18") (pin "2") (pinfunction "2_2") (pintype "passive"))
      (node (ref "R44") (pin "2") (pinfunction "2_2") (pintype "passive"))
      (node (ref "R9") (pin "1") (pinfunction "1_1") (pintype "passive"))
      (node (ref "U20") (pin "2") (pinfunction "VOUT_2") (pintype "passive"))
      (node (ref "U5") (pin "A1") (pinfunction "VDDQ_A1") (pintype "power_in"))
      (node (ref "U5") (pin "A8") (pinfunction "VDDQ_A8") (pintype "power_in"))
      (node (ref "U5") (pin "B2") (pinfunction "VDD_B2") (pintype "power_in"))
      (node (ref "U5") (pin "C1") (pinfunction "VDDQ_C1") (pintype "power_in"))
      (node (ref "U5") (pin "C9") (pinfunction "VDDQ_C9") (pintype "power_in"))
      (node (ref "U5") (pin "D2") (pinfunction "VDDQ_D2") (pintype "power_in"))
      (node (ref "U5") (pin "D9") (pinfunction "VDD_D9") (pintype "power_in"))
      (node (ref "U5") (pin "E9") (pinfunction "VDDQ_E9") (pintype "power_in"))
      (node (ref "U5") (pin "F1") (pinfunction "VDDQ_F1") (pintype "power_in"))
      (node (ref "U5") (pin "G7") (pinfunction "VDD_G7") (pintype "power_in"))
      (node (ref "U5") (pin "H2") (pinfunction "VDDQ_H2") (pintype "power_in"))
      (node (ref "U5") (pin "H9") (pinfunction "VDDQ_H9") (pintype "power_in"))
      (node (ref "U5") (pin "K2") (pinfunction "VDD_K2") (pintype "power_in"))
      (node (ref "U5") (pin "K8") (pinfunction "VDD_K8") (pintype "power_in"))
      (node (ref "U5") (pin "N1") (pinfunction "VDD_N1") (pintype "power_in"))
      (node (ref "U5") (pin "N9") (pinfunction "VDD_N9") (pintype "power_in"))
      (node (ref "U5") (pin "R1") (pinfunction "VDD_R1") (pintype "power_in"))
      (node (ref "U5") (pin "R9") (pinfunction "VDD_R9") (pintype "power_in"))
      (node (ref "U7") (pin "2") (pinfunction "VIN_2") (pintype "power_in"))
    )
    (net (code "65") (name "VSYS") (class "Default")
      (node (ref "C132") (pin "1") (pinfunction "1_1") (pintype "passive"))
      (node (ref "U20") (pin "7") (pinfunction "PVIN_7") (pintype "power_in"))
      (node (ref "U20") (pin "8") (pinfunction "PVIN_8") (pintype "power_in"))
      (node (ref "U20") (pin "9") (pinfunction "VCC_9") (pintype "power_in"))
    )
    (net (code "66") (name "unconnected-(RN7-A-Pad1)") (class "Default")
      (node (ref "RN7") (pin "1") (pinfunction "A_1") (pintype "passive"))
    )
    (net (code "67") (name "unconnected-(U7-PGOOD-Pad9)") (class "Default")
      (node (ref "U7") (pin "9") (pinfunction "PGOOD_9") (pintype "open_collector"))
    )
  )
)
